# CLOCK.net
KiCad netlist of a schematic drawn in Altium Designer
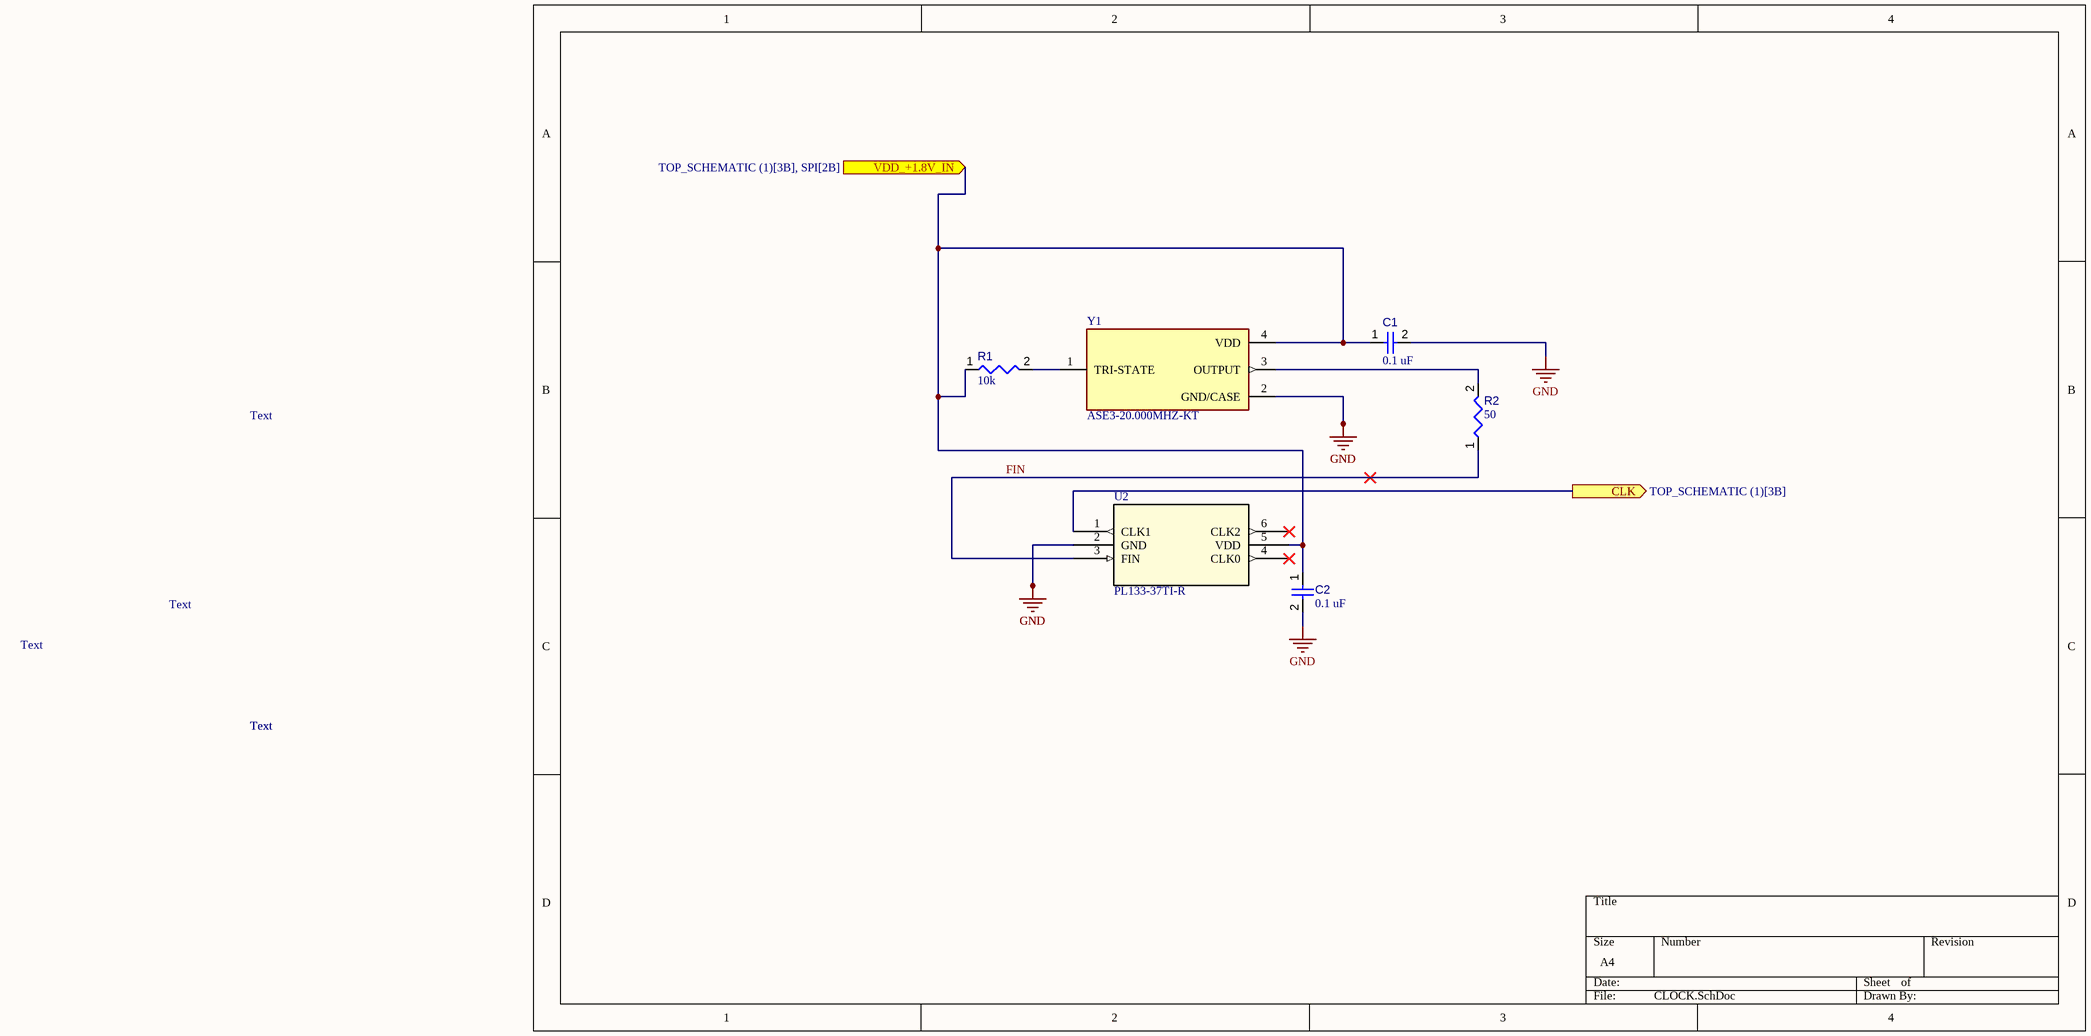
[diagram p0: CLOCK.SchDoc]

(export (version "E")
  (design (tool "Eeschema 10.0.6"))
  (components
    (comp (ref "C1")
      (value "0.1 uF")
      (footprint "CAPC1608X90X40ML10T20")
      (description "Chip Capacitor, 0.1 uF 0603")
      (fields (field (name "TOLERANCE") "5%") (field (name "Comment") "Capacitor 0.1 uF"))
      (libsource (lib "Wilbert Román") (part "CAP-NP-2"))
    )
    (comp (ref "C2")
      (value "0.1 uF")
      (footprint "CAPC1608X90X40ML10T20")
      (description "Chip Capacitor, 0.1 uF 0603")
      (fields (field (name "TOLERANCE") "5%") (field (name "Comment") "Capacitor 0.1 uF"))
      (libsource (lib "Wilbert Román") (part "CAP-NP-2"))
    )
    (comp (ref "R1")
      (value "10k")
      (footprint "RESC2013X50X35ML15T15")
      (description "Chip Resistor, 10 KOhm, +/- 1%, 125 mW, -55 to 155 degC, 0805 (2012 Metric)")
      (fields (field (name "TOLERANCE") "1%") (field (name "POWER") "125mW"))
      (libsource (lib "Wilbert Román") (part "RES-2"))
    )
    (comp (ref "R2")
      (value "50")
      (footprint "RESC1608X55X25ML10T15")
      (description "Chip Resistor, 50 Ohm 0603")
      (fields (field (name "POWER") "100mW") (field (name "TOLERANCE") "1%"))
      (libsource (lib "Wilbert Román") (part "RES-2"))
    )
    (comp (ref "U2")
      (value "PL133-37TI-R")
      (footprint "SOT-23-6_MC_MCH")
      (description "Description")
      (fields (field (name "COPYRIGHT") "Copyright (C) 2025 Ultra Librarian. All rights reserved."))
      (libsource (lib "PL133-37TI-R") (part "PL133-37TI-R"))
    )
    (comp (ref "Y1")
      (value "ASE3-20.000MHZ-KT")
      (footprint "XTAL_ASE3-20.000MHZ-KT")
      (libsource (lib "ASE3-20.000MHZ-KT") (part "ASE3-20.000MHZ-KT"))
    )
  )
  (nets
    (net (code "1") (name "/CLK") (class "Default")
      (node (ref "U2") (pin "1") (pinfunction "CLK1_1") (pintype "output"))
    )
    (net (code "2") (name "/FIN") (class "Default")
      (node (ref "R2") (pin "1") (pinfunction "1_1") (pintype "passive"))
      (node (ref "U2") (pin "3") (pinfunction "FIN_3") (pintype "input"))
    )
    (net (code "3") (name "/VDD_+1.8V_IN") (class "Default")
      (node (ref "C1") (pin "1") (pinfunction "1_1") (pintype "passive"))
      (node (ref "C2") (pin "1") (pinfunction "1_1") (pintype "passive"))
      (node (ref "R1") (pin "1") (pinfunction "1_1") (pintype "passive"))
      (node (ref "U2") (pin "5") (pinfunction "VDD_5") (pintype "power_in"))
      (node (ref "Y1") (pin "4") (pinfunction "VDD_4") (pintype "power_in"))
    )
    (net (code "4") (name "GND") (class "Default")
      (node (ref "C1") (pin "2") (pinfunction "2_2") (pintype "passive"))
      (node (ref "C2") (pin "2") (pinfunction "2_2") (pintype "passive"))
      (node (ref "U2") (pin "2") (pinfunction "GND_2") (pintype "power_in"))
      (node (ref "Y1") (pin "2") (pinfunction "GND/CASE_2") (pintype "power_in"))
    )
    (net (code "5") (name "Net-(Y1-OUTPUT)") (class "Default")
      (node (ref "R2") (pin "2") (pinfunction "2_2") (pintype "passive"))
      (node (ref "Y1") (pin "3") (pinfunction "OUTPUT_3") (pintype "output"))
    )
    (net (code "6") (name "Net-(Y1-TRI-STATE)") (class "Default")
      (node (ref "R1") (pin "2") (pinfunction "2_2") (pintype "passive"))
      (node (ref "Y1") (pin "1") (pinfunction "TRI-STATE_1") (pintype "passive"))
    )
    (net (code "7") (name "unconnected-(U2-CLK0-Pad4)") (class "Default")
      (node (ref "U2") (pin "4") (pinfunction "CLK0_4") (pintype "output+no_connect"))
    )
    (net (code "8") (name "unconnected-(U2-CLK2-Pad6)") (class "Default")
      (node (ref "U2") (pin "6") (pinfunction "CLK2_6") (pintype "output+no_connect"))
    )
  )
)
